# Analog.net
KiCad netlist of a schematic drawn in Altium Designer
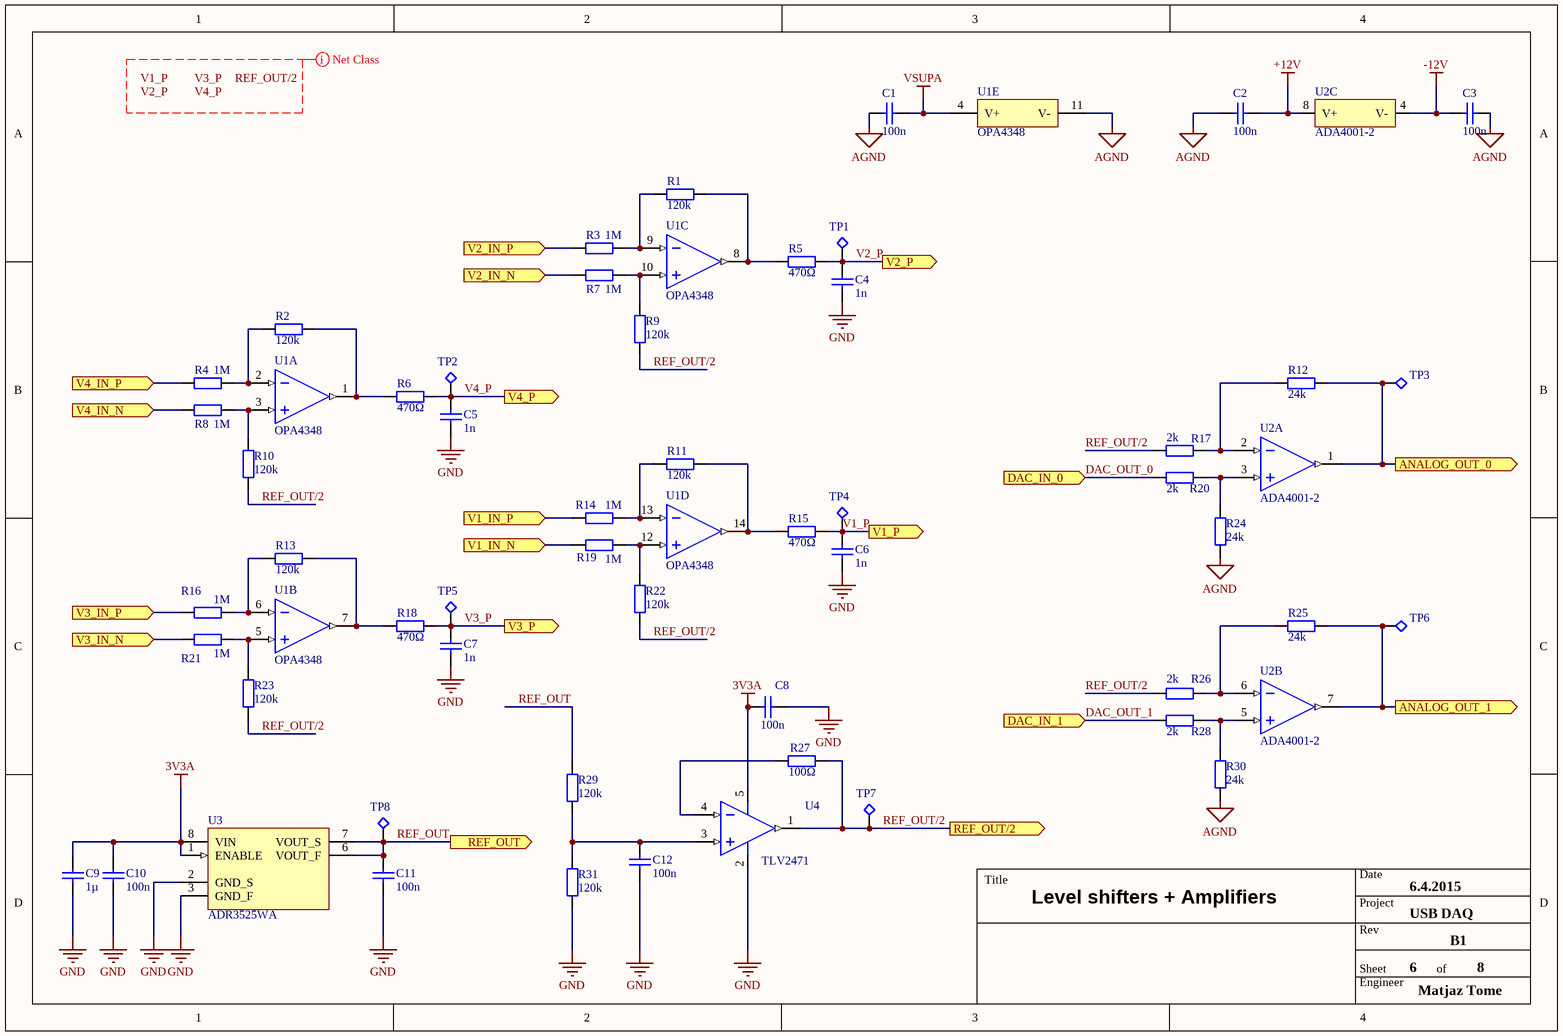
[diagram p0: Analog.SchDoc]

(export (version "E")
  (design (tool "Eeschema 10.0.6"))
  (components
    (comp (ref "C1")
      (value "100n")
      (footprint "0603C")
      (description "ceramic X7R SMD capacitor smd 0603 100nF 16V")
      (fields (field (name "PART NUMBER") "RSC0013") (field (name "MANUFACTURER") "Murata"))
      (libsource (lib "components") (part "Capacitor"))
    )
    (comp (ref "C2")
      (value "100n")
      (footprint "0603C")
      (description "ceramic X7R SMD capacitor smd 0603 100nF 16V")
      (fields (field (name "PART NUMBER") "RSC0013") (field (name "MANUFACTURER") "Murata"))
      (libsource (lib "components") (part "Capacitor"))
    )
    (comp (ref "C3")
      (value "100n")
      (footprint "0603C")
      (description "ceramic X7R SMD capacitor smd 0603 100nF 16V")
      (fields (field (name "PART NUMBER") "RSC0013") (field (name "MANUFACTURER") "Murata"))
      (libsource (lib "components") (part "Capacitor"))
    )
    (comp (ref "C4")
      (value "1n")
      (footprint "0603C")
      (description "ceramic X7R SMD capacitor smd 0603 1nF 100V")
      (fields (field (name "PART NUMBER") "RSC0016") (field (name "MANUFACTURER") "Kemet"))
      (libsource (lib "components") (part "Capacitor"))
    )
    (comp (ref "C5")
      (value "1n")
      (footprint "0603C")
      (description "ceramic X7R SMD capacitor smd 0603 1nF 100V")
      (fields (field (name "PART NUMBER") "RSC0016") (field (name "MANUFACTURER") "Kemet"))
      (libsource (lib "components") (part "Capacitor"))
    )
    (comp (ref "C6")
      (value "1n")
      (footprint "0603C")
      (description "ceramic X7R SMD capacitor smd 0603 1nF 100V")
      (fields (field (name "PART NUMBER") "RSC0016") (field (name "MANUFACTURER") "Kemet"))
      (libsource (lib "components") (part "Capacitor"))
    )
    (comp (ref "C7")
      (value "1n")
      (footprint "0603C")
      (description "ceramic X7R SMD capacitor smd 0603 1nF 100V")
      (fields (field (name "PART NUMBER") "RSC0016") (field (name "MANUFACTURER") "Kemet"))
      (libsource (lib "components") (part "Capacitor"))
    )
    (comp (ref "C8")
      (value "100n")
      (footprint "0603C")
      (description "ceramic X7R SMD capacitor smd 0603 100nF 16V")
      (fields (field (name "PART NUMBER") "RSC0013") (field (name "MANUFACTURER") "Murata"))
      (libsource (lib "components") (part "Capacitor"))
    )
    (comp (ref "C9")
      (value "1µ")
      (footprint "0603C")
      (description "ceramic X5R SMD capacitor smd 0603 1µF 50V")
      (fields (field (name "PART NUMBER") "ZSC0003") (field (name "MANUFACTURER") "Murata"))
      (libsource (lib "components") (part "Capacitor"))
    )
    (comp (ref "C10")
      (value "100n")
      (footprint "0603C")
      (description "ceramic X7R SMD capacitor smd 0603 100nF 16V")
      (fields (field (name "PART NUMBER") "RSC0013") (field (name "MANUFACTURER") "Murata"))
      (libsource (lib "components") (part "Capacitor"))
    )
    (comp (ref "C11")
      (value "100n")
      (footprint "0603C")
      (description "ceramic X7R SMD capacitor smd 0603 100nF 16V")
      (fields (field (name "PART NUMBER") "RSC0013") (field (name "MANUFACTURER") "Murata"))
      (libsource (lib "components") (part "Capacitor"))
    )
    (comp (ref "C12")
      (value "100n")
      (footprint "0603C")
      (description "ceramic X7R SMD capacitor smd 0603 100nF 16V")
      (fields (field (name "PART NUMBER") "RSC0013") (field (name "MANUFACTURER") "Murata"))
      (libsource (lib "components") (part "Capacitor"))
    )
    (comp (ref "R1")
      (value "120k")
      (footprint "0603R")
      (description "resistor smd 0603 120kΩ 0.1% 0.1w")
      (fields (field (name "PART NUMBER") "ZRS0007") (field (name "MANUFACTURER") "Panasonic"))
      (libsource (lib "") (part "Resistor_2"))
    )
    (comp (ref "R2")
      (value "120k")
      (footprint "0603R")
      (description "resistor smd 0603 120kΩ 0.1% 0.1w")
      (fields (field (name "PART NUMBER") "ZRS0007") (field (name "MANUFACTURER") "Panasonic"))
      (libsource (lib "") (part "Resistor_2"))
    )
    (comp (ref "R3")
      (value "1M")
      (footprint "0603R")
      (description "resistor smd 0603 1MΩ 0.1% 0.1w")
      (fields (field (name "PART NUMBER") "ZRS0005") (field (name "MANUFACTURER") "TE Connectivity"))
      (libsource (lib "") (part "Resistor_2"))
    )
    (comp (ref "R4")
      (value "1M")
      (footprint "0603R")
      (description "resistor smd 0603 1MΩ 0.1% 0.1w")
      (fields (field (name "PART NUMBER") "ZRS0005") (field (name "MANUFACTURER") "TE Connectivity"))
      (libsource (lib "") (part "Resistor_2"))
    )
    (comp (ref "R5")
      (value "470Ω")
      (footprint "0603R")
      (description "resistor smd 0603 470Ω 5% 0.1w")
      (fields (field (name "PART NUMBER") "XRS0039") (field (name "MANUFACTURER") "Multicomp"))
      (libsource (lib "") (part "Resistor_2"))
    )
    (comp (ref "R6")
      (value "470Ω")
      (footprint "0603R")
      (description "resistor smd 0603 470Ω 5% 0.1w")
      (fields (field (name "PART NUMBER") "XRS0039") (field (name "MANUFACTURER") "Multicomp"))
      (libsource (lib "") (part "Resistor_2"))
    )
    (comp (ref "R7")
      (value "1M")
      (footprint "0603R")
      (description "resistor smd 0603 1MΩ 0.1% 0.1w")
      (fields (field (name "PART NUMBER") "ZRS0005") (field (name "MANUFACTURER") "TE Connectivity"))
      (libsource (lib "") (part "Resistor_2"))
    )
    (comp (ref "R8")
      (value "1M")
      (footprint "0603R")
      (description "resistor smd 0603 1MΩ 0.1% 0.1w")
      (fields (field (name "PART NUMBER") "ZRS0005") (field (name "MANUFACTURER") "TE Connectivity"))
      (libsource (lib "") (part "Resistor_2"))
    )
    (comp (ref "R9")
      (value "120k")
      (footprint "0603R")
      (description "resistor smd 0603 120kΩ 0.1% 0.1w")
      (fields (field (name "PART NUMBER") "ZRS0007") (field (name "MANUFACTURER") "Panasonic"))
      (libsource (lib "components") (part "Resistor"))
    )
    (comp (ref "R10")
      (value "120k")
      (footprint "0603R")
      (description "resistor smd 0603 120kΩ 0.1% 0.1w")
      (fields (field (name "PART NUMBER") "ZRS0007") (field (name "MANUFACTURER") "Panasonic"))
      (libsource (lib "components") (part "Resistor"))
    )
    (comp (ref "R11")
      (value "120k")
      (footprint "0603R")
      (description "resistor smd 0603 120kΩ 0.1% 0.1w")
      (fields (field (name "PART NUMBER") "ZRS0007") (field (name "MANUFACTURER") "Panasonic"))
      (libsource (lib "") (part "Resistor_2"))
    )
    (comp (ref "R12")
      (value "24k")
      (footprint "0603R")
      (description "resistor smd 0603 24kΩ 0.1% 0.1w")
      (fields (field (name "PART NUMBER") "ZRS0008") (field (name "MANUFACTURER") "Welwyn"))
      (libsource (lib "") (part "Resistor_2"))
    )
    (comp (ref "R13")
      (value "120k")
      (footprint "0603R")
      (description "resistor smd 0603 120kΩ 0.1% 0.1w")
      (fields (field (name "PART NUMBER") "ZRS0007") (field (name "MANUFACTURER") "Panasonic"))
      (libsource (lib "") (part "Resistor_2"))
    )
    (comp (ref "R14")
      (value "1M")
      (footprint "0603R")
      (description "resistor smd 0603 1MΩ 0.1% 0.1w")
      (fields (field (name "PART NUMBER") "ZRS0005") (field (name "MANUFACTURER") "TE Connectivity"))
      (libsource (lib "") (part "Resistor_2"))
    )
    (comp (ref "R15")
      (value "470Ω")
      (footprint "0603R")
      (description "resistor smd 0603 470Ω 5% 0.1w")
      (fields (field (name "PART NUMBER") "XRS0039") (field (name "MANUFACTURER") "Multicomp"))
      (libsource (lib "") (part "Resistor_2"))
    )
    (comp (ref "R16")
      (value "1M")
      (footprint "0603R")
      (description "resistor smd 0603 1MΩ 0.1% 0.1w")
      (fields (field (name "PART NUMBER") "ZRS0005") (field (name "MANUFACTURER") "TE Connectivity"))
      (libsource (lib "") (part "Resistor_2"))
    )
    (comp (ref "R17")
      (value "2k")
      (footprint "0603R")
      (description "resistor smd 0603 2kΩ 0.1% 0.1w")
      (fields (field (name "PART NUMBER") "ZRS0001") (field (name "MANUFACTURER") "Susumu"))
      (libsource (lib "") (part "Resistor_2"))
    )
    (comp (ref "R18")
      (value "470Ω")
      (footprint "0603R")
      (description "resistor smd 0603 470Ω 5% 0.1w")
      (fields (field (name "PART NUMBER") "XRS0039") (field (name "MANUFACTURER") "Multicomp"))
      (libsource (lib "") (part "Resistor_2"))
    )
    (comp (ref "R19")
      (value "1M")
      (footprint "0603R")
      (description "resistor smd 0603 1MΩ 0.1% 0.1w")
      (fields (field (name "PART NUMBER") "ZRS0005") (field (name "MANUFACTURER") "TE Connectivity"))
      (libsource (lib "") (part "Resistor_2"))
    )
    (comp (ref "R20")
      (value "2k")
      (footprint "0603R")
      (description "resistor smd 0603 2kΩ 0.1% 0.1w")
      (fields (field (name "PART NUMBER") "ZRS0001") (field (name "MANUFACTURER") "Susumu"))
      (libsource (lib "") (part "Resistor_2"))
    )
    (comp (ref "R21")
      (value "1M")
      (footprint "0603R")
      (description "resistor smd 0603 1MΩ 0.1% 0.1w")
      (fields (field (name "PART NUMBER") "ZRS0005") (field (name "MANUFACTURER") "TE Connectivity"))
      (libsource (lib "") (part "Resistor_2"))
    )
    (comp (ref "R22")
      (value "120k")
      (footprint "0603R")
      (description "resistor smd 0603 120kΩ 0.1% 0.1w")
      (fields (field (name "PART NUMBER") "ZRS0007") (field (name "MANUFACTURER") "Panasonic"))
      (libsource (lib "components") (part "Resistor"))
    )
    (comp (ref "R23")
      (value "120k")
      (footprint "0603R")
      (description "resistor smd 0603 120kΩ 0.1% 0.1w")
      (fields (field (name "PART NUMBER") "ZRS0007") (field (name "MANUFACTURER") "Panasonic"))
      (libsource (lib "components") (part "Resistor"))
    )
    (comp (ref "R24")
      (value "24k")
      (footprint "0603R")
      (description "resistor smd 0603 24kΩ 0.1% 0.1w")
      (fields (field (name "PART NUMBER") "ZRS0008") (field (name "MANUFACTURER") "Welwyn"))
      (libsource (lib "components") (part "Resistor"))
    )
    (comp (ref "R25")
      (value "24k")
      (footprint "0603R")
      (description "resistor smd 0603 24kΩ 0.1% 0.1w")
      (fields (field (name "PART NUMBER") "ZRS0008") (field (name "MANUFACTURER") "Welwyn"))
      (libsource (lib "") (part "Resistor_1"))
    )
    (comp (ref "R26")
      (value "2k")
      (footprint "0603R")
      (description "resistor smd 0603 2kΩ 0.1% 0.1w")
      (fields (field (name "PART NUMBER") "ZRS0001") (field (name "MANUFACTURER") "Susumu"))
      (libsource (lib "") (part "Resistor_2"))
    )
    (comp (ref "R27")
      (value "100Ω")
      (footprint "0603R")
      (description "resistor smd 0603 100Ω 5% 0.1w")
      (fields (field (name "PART NUMBER") "XRS0016") (field (name "MANUFACTURER") "Multicomp"))
      (libsource (lib "") (part "Resistor_2"))
    )
    (comp (ref "R28")
      (value "2k")
      (footprint "0603R")
      (description "resistor smd 0603 2kΩ 0.1% 0.1w")
      (fields (field (name "PART NUMBER") "ZRS0001") (field (name "MANUFACTURER") "Susumu"))
      (libsource (lib "") (part "Resistor_2"))
    )
    (comp (ref "R29")
      (value "120k")
      (footprint "0603R")
      (description "resistor smd 0603 120kΩ 0.1% 0.1w")
      (fields (field (name "PART NUMBER") "ZRS0007") (field (name "MANUFACTURER") "Panasonic"))
      (libsource (lib "components") (part "Resistor"))
    )
    (comp (ref "R30")
      (value "24k")
      (footprint "0603R")
      (description "resistor smd 0603 24kΩ 0.1% 0.1w")
      (fields (field (name "PART NUMBER") "ZRS0008") (field (name "MANUFACTURER") "Welwyn"))
      (libsource (lib "components") (part "Resistor"))
    )
    (comp (ref "R31")
      (value "120k")
      (footprint "0603R")
      (description "resistor smd 0603 120kΩ 0.1% 0.1w")
      (fields (field (name "PART NUMBER") "ZRS0007") (field (name "MANUFACTURER") "Panasonic"))
      (libsource (lib "components") (part "Resistor"))
    )
    (comp (ref "TP1")
      (value "testpoint")
      (footprint "TP1_FULL")
      (description "testpoint 1.5mm diameter no hole")
      (fields (field (name "PART NUMBER") "XXC0006"))
      (libsource (lib "components") (part "Test Point"))
    )
    (comp (ref "TP2")
      (value "testpoint")
      (footprint "TP1_FULL")
      (description "testpoint 1.5mm diameter no hole")
      (fields (field (name "PART NUMBER") "XXC0006"))
      (libsource (lib "components") (part "Test Point"))
    )
    (comp (ref "TP3")
      (value "testpoint")
      (footprint "TP1_FULL")
      (description "testpoint 1.5mm diameter no hole")
      (fields (field (name "PART NUMBER") "XXC0006"))
      (libsource (lib "components") (part "Test Point"))
    )
    (comp (ref "TP4")
      (value "testpoint")
      (footprint "TP1_FULL")
      (description "testpoint 1.5mm diameter no hole")
      (fields (field (name "PART NUMBER") "XXC0006"))
      (libsource (lib "components") (part "Test Point"))
    )
    (comp (ref "TP5")
      (value "testpoint")
      (footprint "TP1_FULL")
      (description "testpoint 1.5mm diameter no hole")
      (fields (field (name "PART NUMBER") "XXC0006"))
      (libsource (lib "components") (part "Test Point"))
    )
    (comp (ref "TP6")
      (value "testpoint")
      (footprint "TP1_FULL")
      (description "testpoint 1.5mm diameter no hole")
      (fields (field (name "PART NUMBER") "XXC0006"))
      (libsource (lib "components") (part "Test Point"))
    )
    (comp (ref "TP7")
      (value "testpoint")
      (footprint "TP1_FULL")
      (description "testpoint 1.5mm diameter no hole")
      (fields (field (name "PART NUMBER") "XXC0006"))
      (libsource (lib "components") (part "Test Point"))
    )
    (comp (ref "TP8")
      (value "testpoint")
      (footprint "TP1_FULL")
      (description "testpoint 1.5mm diameter no hole")
      (fields (field (name "PART NUMBER") "XXC0006"))
      (libsource (lib "components") (part "Test Point"))
    )
    (comp (ref "U1")
      (value "OPA4348")
      (footprint "SOIC14")
      (description "1MHz, 45µA, CMOS, Rail-to-Rail OPERATIONAL AMPLIFIERS Value Line Series")
      (fields (field (name "PART NUMBER") "XOG0008") (field (name "MANUFACTURER") "Texas Instruments"))
      (libsource (lib "components") (part "OPAMP_QUAD_1"))
    )
    (comp (ref "U2")
      (value "ADA4001-2")
      (footprint "SOIC8")
      (description "Low Noise, Low Input Bias Current, Rail-to-Rail\r\nOutput, JFET Dual Operational Amplifier")
      (fields (field (name "PART NUMBER") "XOG0003") (field (name "MANUFACTURER") "Analog devices"))
      (libsource (lib "") (part "OPAMP_DUAL_1_1"))
    )
    (comp (ref "U3")
      (value "ADR3525WA")
      (footprint "MSOP8")
      (description "Micropower, High Accuracy\r\nVoltage References")
      (fields (field (name "PART NUMBER") "VRX0002") (field (name "MANUFACTURER") "Analog devices"))
      (libsource (lib "components") (part "ADR3525W"))
    )
    (comp (ref "U4")
      (value "TLV2471")
      (footprint "SOT23-5")
      (fields (field (name "PART NUMBER") "XOG0002") (field (name "MANUFACTURER") "Texas Instruments"))
      (libsource (lib "components") (part "OPAMP_SINGLE_1"))
    )
  )
  (nets
    (net (code "1") (name "+12V") (class "Default")
      (node (ref "C2") (pin "1") (pinfunction "1_1") (pintype "passive"))
      (node (ref "U2") (pin "8") (pinfunction "V+_8") (pintype "power_in"))
    )
    (net (code "2") (name "-12V") (class "Default")
      (node (ref "C3") (pin "2") (pinfunction "2_2") (pintype "passive"))
      (node (ref "U2") (pin "4") (pinfunction "V-_4") (pintype "power_in"))
    )
    (net (code "3") (name "/ANALOG_OUT_0") (class "Default")
      (node (ref "R12") (pin "2") (pinfunction "2_2") (pintype "passive"))
      (node (ref "TP3") (pin "1") (pinfunction "1_1") (pintype "passive"))
      (node (ref "U2") (pin "1") (pinfunction "OUT_1") (pintype "output"))
    )
    (net (code "4") (name "/ANALOG_OUT_1") (class "Default")
      (node (ref "R25") (pin "1") (pinfunction "1_1") (pintype "passive"))
      (node (ref "TP6") (pin "1") (pinfunction "1_1") (pintype "passive"))
      (node (ref "U2") (pin "7") (pinfunction "OUT_7") (pintype "output"))
    )
    (net (code "5") (name "/DAC_OUT_0") (class "Default")
      (node (ref "R20") (pin "1") (pinfunction "1_1") (pintype "passive"))
    )
    (net (code "6") (name "/DAC_OUT_1") (class "Default")
      (node (ref "R28") (pin "1") (pinfunction "1_1") (pintype "passive"))
    )
    (net (code "7") (name "/REF_OUT") (class "Default")
      (node (ref "C11") (pin "2") (pinfunction "2_2") (pintype "passive"))
      (node (ref "R29") (pin "2") (pinfunction "2_2") (pintype "passive"))
      (node (ref "TP8") (pin "1") (pinfunction "1_1") (pintype "passive"))
      (node (ref "U3") (pin "6") (pinfunction "VOUT_F_6") (pintype "power_in"))
      (node (ref "U3") (pin "7") (pinfunction "VOUT_S_7") (pintype "power_in"))
    )
    (net (code "8") (name "/REF_OUT{slash}2") (class "Default")
      (node (ref "R10") (pin "1") (pinfunction "1_1") (pintype "passive"))
      (node (ref "R17") (pin "1") (pinfunction "1_1") (pintype "passive"))
      (node (ref "R22") (pin "1") (pinfunction "1_1") (pintype "passive"))
      (node (ref "R23") (pin "1") (pinfunction "1_1") (pintype "passive"))
      (node (ref "R26") (pin "1") (pinfunction "1_1") (pintype "passive"))
      (node (ref "R27") (pin "2") (pinfunction "2_2") (pintype "passive"))
      (node (ref "R9") (pin "1") (pinfunction "1_1") (pintype "passive"))
      (node (ref "TP7") (pin "1") (pinfunction "1_1") (pintype "passive"))
      (node (ref "U4") (pin "1") (pinfunction "OUT_A_1") (pintype "output"))
    )
    (net (code "9") (name "/V1_IN_N") (class "Default")
      (node (ref "R19") (pin "1") (pinfunction "1_1") (pintype "passive"))
    )
    (net (code "10") (name "/V1_IN_P") (class "Default")
      (node (ref "R14") (pin "1") (pinfunction "1_1") (pintype "passive"))
    )
    (net (code "11") (name "/V1_P") (class "Default")
      (node (ref "C6") (pin "2") (pinfunction "2_2") (pintype "passive"))
      (node (ref "R15") (pin "2") (pinfunction "2_2") (pintype "passive"))
      (node (ref "TP4") (pin "1") (pinfunction "1_1") (pintype "passive"))
    )
    (net (code "12") (name "/V2_IN_N") (class "Default")
      (node (ref "R7") (pin "1") (pinfunction "1_1") (pintype "passive"))
    )
    (net (code "13") (name "/V2_IN_P") (class "Default")
      (node (ref "R3") (pin "1") (pinfunction "1_1") (pintype "passive"))
    )
    (net (code "14") (name "/V2_P") (class "Default")
      (node (ref "C4") (pin "2") (pinfunction "2_2") (pintype "passive"))
      (node (ref "R5") (pin "2") (pinfunction "2_2") (pintype "passive"))
      (node (ref "TP1") (pin "1") (pinfunction "1_1") (pintype "passive"))
    )
    (net (code "15") (name "/V3_IN_N") (class "Default")
      (node (ref "R21") (pin "1") (pinfunction "1_1") (pintype "passive"))
    )
    (net (code "16") (name "/V3_IN_P") (class "Default")
      (node (ref "R16") (pin "1") (pinfunction "1_1") (pintype "passive"))
    )
    (net (code "17") (name "/V3_P") (class "Default")
      (node (ref "C7") (pin "2") (pinfunction "2_2") (pintype "passive"))
      (node (ref "R18") (pin "2") (pinfunction "2_2") (pintype "passive"))
      (node (ref "TP5") (pin "1") (pinfunction "1_1") (pintype "passive"))
    )
    (net (code "18") (name "/V4_IN_N") (class "Default")
      (node (ref "R8") (pin "1") (pinfunction "1_1") (pintype "passive"))
    )
    (net (code "19") (name "/V4_IN_P") (class "Default")
      (node (ref "R4") (pin "1") (pinfunction "1_1") (pintype "passive"))
    )
    (net (code "20") (name "/V4_P") (class "Default")
      (node (ref "C5") (pin "2") (pinfunction "2_2") (pintype "passive"))
      (node (ref "R6") (pin "2") (pinfunction "2_2") (pintype "passive"))
      (node (ref "TP2") (pin "1") (pinfunction "1_1") (pintype "passive"))
    )
    (net (code "21") (name "3V3A") (class "Default")
      (node (ref "C10") (pin "2") (pinfunction "2_2") (pintype "passive"))
      (node (ref "C8") (pin "2") (pinfunction "2_2") (pintype "passive"))
      (node (ref "C9") (pin "2") (pinfunction "2_2") (pintype "passive"))
      (node (ref "U3") (pin "1") (pinfunction "ENABLE_1") (pintype "input"))
      (node (ref "U3") (pin "8") (pinfunction "VIN_8") (pintype "power_in"))
      (node (ref "U4") (pin "5") (pinfunction "V+_5") (pintype "power_in"))
    )
    (net (code "22") (name "AGND") (class "Default")
      (node (ref "C1") (pin "2") (pinfunction "2_2") (pintype "passive"))
      (node (ref "C2") (pin "2") (pinfunction "2_2") (pintype "passive"))
      (node (ref "C3") (pin "1") (pinfunction "1_1") (pintype "passive"))
      (node (ref "R24") (pin "1") (pinfunction "1_1") (pintype "passive"))
      (node (ref "R30") (pin "1") (pinfunction "1_1") (pintype "passive"))
      (node (ref "U1") (pin "11") (pinfunction "V-_11") (pintype "power_in"))
    )
    (net (code "23") (name "GND") (class "Default")
      (node (ref "C10") (pin "1") (pinfunction "1_1") (pintype "passive"))
      (node (ref "C11") (pin "1") (pinfunction "1_1") (pintype "passive"))
      (node (ref "C12") (pin "1") (pinfunction "1_1") (pintype "passive"))
      (node (ref "C4") (pin "1") (pinfunction "1_1") (pintype "passive"))
      (node (ref "C5") (pin "1") (pinfunction "1_1") (pintype "passive"))
      (node (ref "C6") (pin "1") (pinfunction "1_1") (pintype "passive"))
      (node (ref "C7") (pin "1") (pinfunction "1_1") (pintype "passive"))
      (node (ref "C8") (pin "1") (pinfunction "1_1") (pintype "passive"))
      (node (ref "C9") (pin "1") (pinfunction "1_1") (pintype "passive"))
      (node (ref "R31") (pin "1") (pinfunction "1_1") (pintype "passive"))
      (node (ref "U3") (pin "2") (pinfunction "GND_S_2") (pintype "power_in"))
      (node (ref "U3") (pin "3") (pinfunction "GND_F_3") (pintype "power_in"))
      (node (ref "U4") (pin "2") (pinfunction "V-_2") (pintype "power_in"))
    )
    (net (code "24") (name "Net-(U1A-+IN_A)") (class "Default")
      (node (ref "R10") (pin "2") (pinfunction "2_2") (pintype "passive"))
      (node (ref "R8") (pin "2") (pinfunction "2_2") (pintype "passive"))
      (node (ref "U1") (pin "3") (pinfunction "+IN_A_3") (pintype "input"))
    )
    (net (code "25") (name "Net-(U1A--IN_A)") (class "Default")
      (node (ref "R2") (pin "1") (pinfunction "1_1") (pintype "passive"))
      (node (ref "R4") (pin "2") (pinfunction "2_2") (pintype "passive"))
      (node (ref "U1") (pin "2") (pinfunction "-IN_A_2") (pintype "input"))
    )
    (net (code "26") (name "Net-(U1A-OUT_A)") (class "Default")
      (node (ref "R2") (pin "2") (pinfunction "2_2") (pintype "passive"))
      (node (ref "R6") (pin "1") (pinfunction "1_1") (pintype "passive"))
      (node (ref "U1") (pin "1") (pinfunction "OUT_A_1") (pintype "output"))
    )
    (net (code "27") (name "Net-(U1B-+IN_B)") (class "Default")
      (node (ref "R21") (pin "2") (pinfunction "2_2") (pintype "passive"))
      (node (ref "R23") (pin "2") (pinfunction "2_2") (pintype "passive"))
      (node (ref "U1") (pin "5") (pinfunction "+IN_B_5") (pintype "input"))
    )
    (net (code "28") (name "Net-(U1B--IN_B)") (class "Default")
      (node (ref "R13") (pin "1") (pinfunction "1_1") (pintype "passive"))
      (node (ref "R16") (pin "2") (pinfunction "2_2") (pintype "passive"))
      (node (ref "U1") (pin "6") (pinfunction "-IN_B_6") (pintype "input"))
    )
    (net (code "29") (name "Net-(U1B-OUT_B)") (class "Default")
      (node (ref "R13") (pin "2") (pinfunction "2_2") (pintype "passive"))
      (node (ref "R18") (pin "1") (pinfunction "1_1") (pintype "passive"))
      (node (ref "U1") (pin "7") (pinfunction "OUT_B_7") (pintype "output"))
    )
    (net (code "30") (name "Net-(U1C-+IN_C)") (class "Default")
      (node (ref "R7") (pin "2") (pinfunction "2_2") (pintype "passive"))
      (node (ref "R9") (pin "2") (pinfunction "2_2") (pintype "passive"))
      (node (ref "U1") (pin "10") (pinfunction "+IN_C_10") (pintype "input"))
    )
    (net (code "31") (name "Net-(U1C--IN_C)") (class "Default")
      (node (ref "R1") (pin "1") (pinfunction "1_1") (pintype "passive"))
      (node (ref "R3") (pin "2") (pinfunction "2_2") (pintype "passive"))
      (node (ref "U1") (pin "9") (pinfunction "-IN_C_9") (pintype "input"))
    )
    (net (code "32") (name "Net-(U1C-OUT_C)") (class "Default")
      (node (ref "R1") (pin "2") (pinfunction "2_2") (pintype "passive"))
      (node (ref "R5") (pin "1") (pinfunction "1_1") (pintype "passive"))
      (node (ref "U1") (pin "8") (pinfunction "OUT_C_8") (pintype "output"))
    )
    (net (code "33") (name "Net-(U1D-+IN_D)") (class "Default")
      (node (ref "R19") (pin "2") (pinfunction "2_2") (pintype "passive"))
      (node (ref "R22") (pin "2") (pinfunction "2_2") (pintype "passive"))
      (node (ref "U1") (pin "12") (pinfunction "+IN_D_12") (pintype "input"))
    )
    (net (code "34") (name "Net-(U1D--IN_D)") (class "Default")
      (node (ref "R11") (pin "1") (pinfunction "1_1") (pintype "passive"))
      (node (ref "R14") (pin "2") (pinfunction "2_2") (pintype "passive"))
      (node (ref "U1") (pin "13") (pinfunction "-IN_D_13") (pintype "input"))
    )
    (net (code "35") (name "Net-(U1D-OUT_D)") (class "Default")
      (node (ref "R11") (pin "2") (pinfunction "2_2") (pintype "passive"))
      (node (ref "R15") (pin "1") (pinfunction "1_1") (pintype "passive"))
      (node (ref "U1") (pin "14") (pinfunction "OUT_D_14") (pintype "output"))
    )
    (net (code "36") (name "Net-(U2A-IN+)") (class "Default")
      (node (ref "R20") (pin "2") (pinfunction "2_2") (pintype "passive"))
      (node (ref "R24") (pin "2") (pinfunction "2_2") (pintype "passive"))
      (node (ref "U2") (pin "3") (pinfunction "IN+_3") (pintype "input"))
    )
    (net (code "37") (name "Net-(U2A-IN-)") (class "Default")
      (node (ref "R12") (pin "1") (pinfunction "1_1") (pintype "passive"))
      (node (ref "R17") (pin "2") (pinfunction "2_2") (pintype "passive"))
      (node (ref "U2") (pin "2") (pinfunction "IN-_2") (pintype "input"))
    )
    (net (code "38") (name "Net-(U2B-IN2+)") (class "Default")
      (node (ref "R28") (pin "2") (pinfunction "2_2") (pintype "passive"))
      (node (ref "R30") (pin "2") (pinfunction "2_2") (pintype "passive"))
      (node (ref "U2") (pin "5") (pinfunction "IN2+_5") (pintype "input"))
    )
    (net (code "39") (name "Net-(U2B-IN2-)") (class "Default")
      (node (ref "R25") (pin "2") (pinfunction "2_2") (pintype "passive"))
      (node (ref "R26") (pin "2") (pinfunction "2_2") (pintype "passive"))
      (node (ref "U2") (pin "6") (pinfunction "IN2-_6") (pintype "input"))
    )
    (net (code "40") (name "Net-(U4-+IN_A)") (class "Default")
      (node (ref "C12") (pin "2") (pinfunction "2_2") (pintype "passive"))
      (node (ref "R29") (pin "1") (pinfunction "1_1") (pintype "passive"))
      (node (ref "R31") (pin "2") (pinfunction "2_2") (pintype "passive"))
      (node (ref "U4") (pin "3") (pinfunction "+IN_A_3") (pintype "input"))
    )
    (net (code "41") (name "Net-(U4--IN_A)") (class "Default")
      (node (ref "R27") (pin "1") (pinfunction "1_1") (pintype "passive"))
      (node (ref "U4") (pin "4") (pinfunction "-IN_A_4") (pintype "input"))
    )
    (net (code "42") (name "VSUPA") (class "Default")
      (node (ref "C1") (pin "1") (pinfunction "1_1") (pintype "passive"))
      (node (ref "U1") (pin "4") (pinfunction "V+_4") (pintype "power_in"))
    )
  )
)
